# FanControl.net
KiCad netlist of a schematic drawn in EAGLE
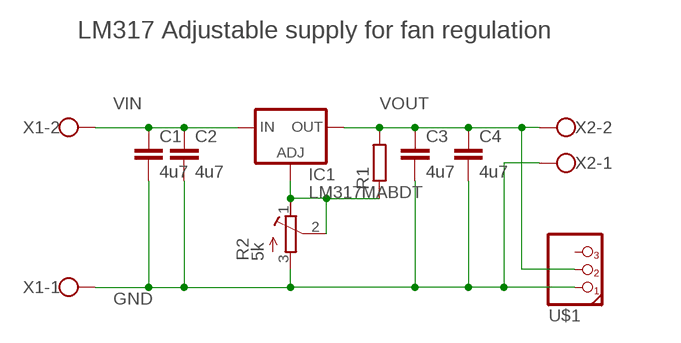
[diagram p0: schematic, sheet 1]

(export (version "E")
  (design (tool "Eeschema 10.0.6"))
  (components
    (comp (ref "C1")
      (value "4u7")
      (footprint "eagle-import:C0805")
      (libsource (lib "eagle-import") (part "C-EUC0805"))
    )
    (comp (ref "C2")
      (value "4u7")
      (footprint "eagle-import:C0805")
      (libsource (lib "eagle-import") (part "C-EUC0805"))
    )
    (comp (ref "C3")
      (value "4u7")
      (footprint "eagle-import:C0805")
      (libsource (lib "eagle-import") (part "C-EUC0805"))
    )
    (comp (ref "C4")
      (value "4u7")
      (footprint "eagle-import:C0805")
      (libsource (lib "eagle-import") (part "C-EUC0805"))
    )
    (comp (ref "IC1")
      (value "LM317MABDT")
      (footprint "eagle-import:DPACK")
      (libsource (lib "eagle-import") (part "v-reg_LM317?MABDT"))
    )
    (comp (ref "R1")
      (value "R-EU_R1206")
      (footprint "eagle-import:R1206")
      (libsource (lib "eagle-import") (part "R-EU_R1206"))
    )
    (comp (ref "R2")
      (value "5k")
      (footprint "eagle-import:RTRIMT93YA")
      (libsource (lib "eagle-import") (part "R-TRIMMT93YA"))
    )
    (comp (ref "U$1")
      (value "PINHD-1X3")
      (footprint "eagle-import:1X03")
      (libsource (lib "eagle-import") (part "PINHD-1X3"))
    )
    (comp (ref "X1")
      (value "SCREWTERMINATOR1X2")
      (footprint "eagle-import:W237-102")
      (fields (field (name "MPN") "237-102"))
      (libsource (lib "eagle-import") (part "SCREWTERMINATOR1X2"))
    )
    (comp (ref "X2")
      (value "SCREWTERMINATOR1X2")
      (footprint "eagle-import:W237-102")
      (fields (field (name "MPN") "237-102"))
      (libsource (lib "eagle-import") (part "SCREWTERMINATOR1X2"))
    )
  )
  (nets
    (net (code "1") (name "/GND") (class "Default")
      (node (ref "C1") (pin "2") (pinfunction "2_2") (pintype "passive"))
      (node (ref "C2") (pin "2") (pinfunction "2_2") (pintype "passive"))
      (node (ref "C3") (pin "2") (pinfunction "2_2") (pintype "passive"))
      (node (ref "C4") (pin "2") (pinfunction "2_2") (pintype "passive"))
      (node (ref "R2") (pin "3") (pinfunction "A_3") (pintype "passive"))
      (node (ref "U$1") (pin "1") (pinfunction "1_1") (pintype "passive"))
      (node (ref "X1") (pin "1") (pinfunction "KL_1") (pintype "passive"))
      (node (ref "X2") (pin "1") (pinfunction "KL_1") (pintype "passive"))
    )
    (net (code "2") (name "/VIN") (class "Default")
      (node (ref "C1") (pin "1") (pinfunction "1_1") (pintype "passive"))
      (node (ref "C2") (pin "1") (pinfunction "1_1") (pintype "passive"))
      (node (ref "IC1") (pin "3") (pinfunction "IN_3") (pintype "input"))
      (node (ref "X1") (pin "2") (pinfunction "KL_2") (pintype "passive"))
    )
    (net (code "3") (name "/VOUT") (class "Default")
      (node (ref "C3") (pin "1") (pinfunction "1_1") (pintype "passive"))
      (node (ref "C4") (pin "1") (pinfunction "1_1") (pintype "passive"))
      (node (ref "IC1") (pin "4") (pinfunction "OUT_4") (pintype "passive"))
      (node (ref "R1") (pin "2") (pinfunction "2_2") (pintype "passive"))
      (node (ref "U$1") (pin "2") (pinfunction "2_2") (pintype "passive"))
      (node (ref "X2") (pin "2") (pinfunction "KL_2") (pintype "passive"))
    )
    (net (code "4") (name "Net-(IC1-ADJ)") (class "Default")
      (node (ref "IC1") (pin "1") (pinfunction "ADJ_1") (pintype "input"))
      (node (ref "R1") (pin "1") (pinfunction "1_1") (pintype "passive"))
      (node (ref "R2") (pin "1") (pinfunction "E_1") (pintype "passive"))
      (node (ref "R2") (pin "2") (pinfunction "S_2") (pintype "passive"))
    )
    (net (code "5") (name "unconnected-(U$1-Pad3)") (class "Default")
      (node (ref "U$1") (pin "3") (pinfunction "3_3") (pintype "passive"))
    )
  )
)
